# SCH_KTH7823_V1_0.net
KiCad netlist of a schematic drawn in EasyEDA
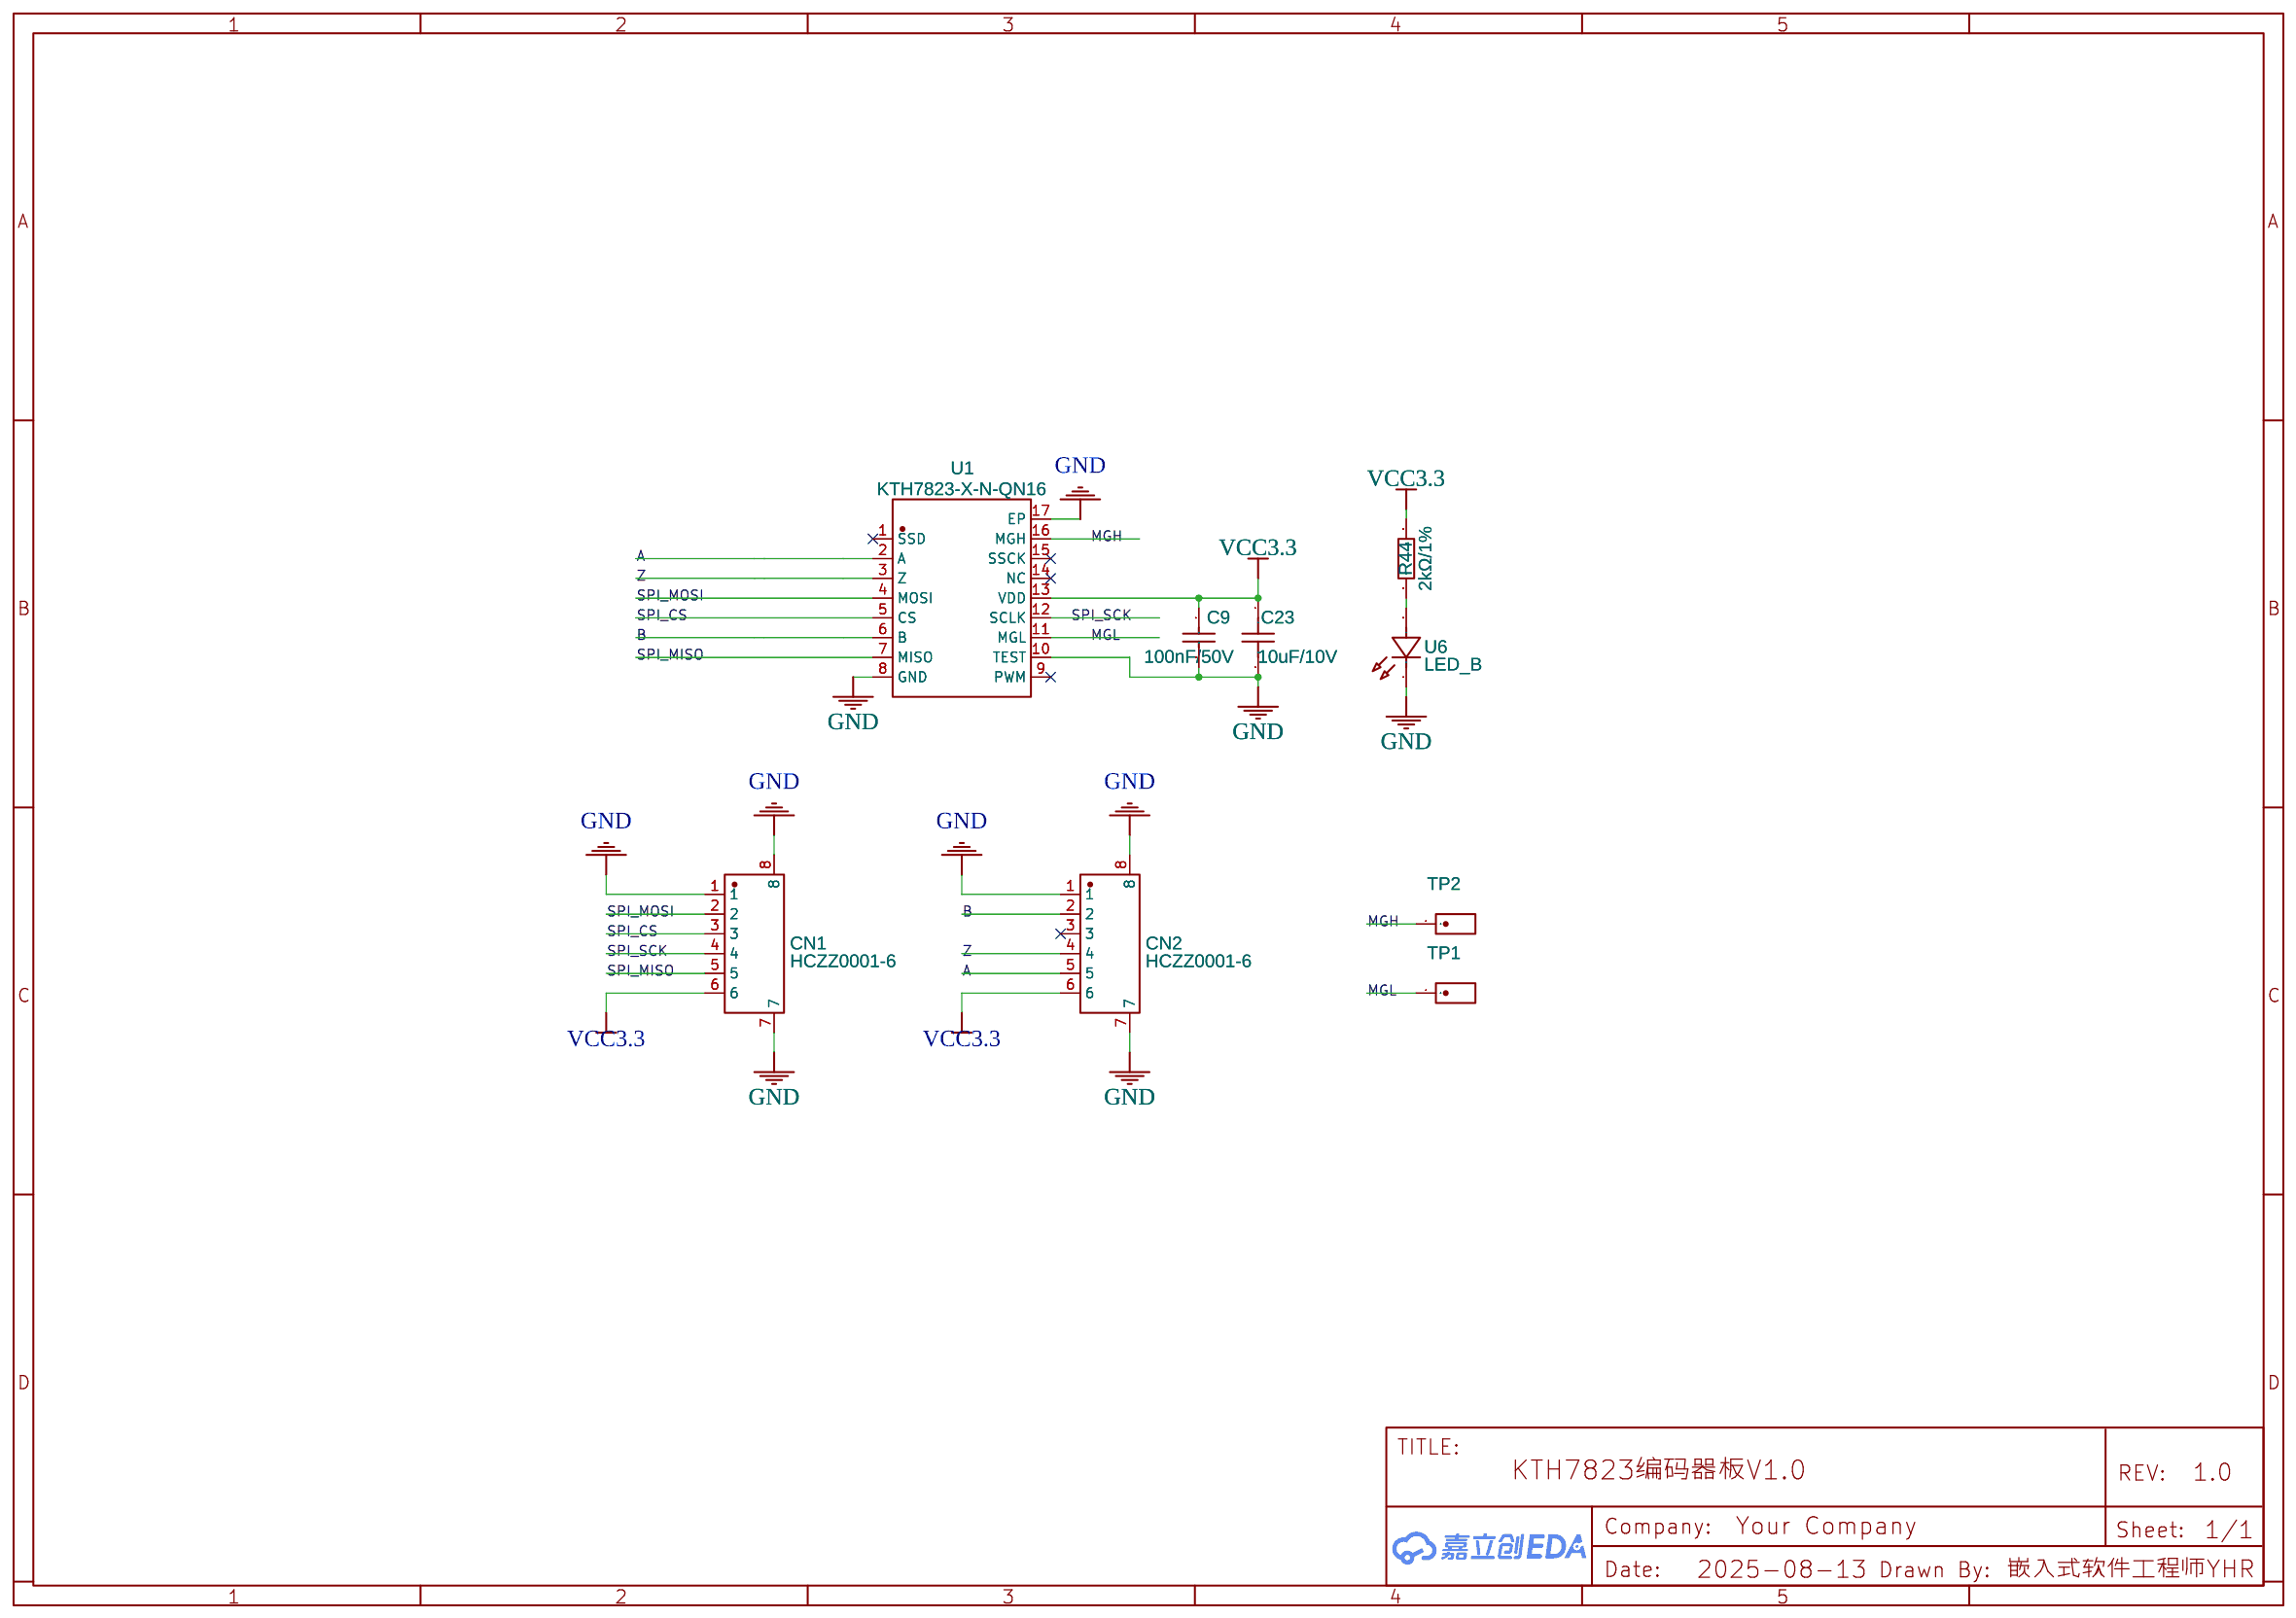
[diagram p0: schematic sheet]

(export (version "E")
  (design (tool "Eeschema 10.0.6"))
  (components
    (comp (ref "C9")
      (value "100nF/50V")
      (fields
        (field (name "Manufacturer Part") "CC0402KRX7R9BB104")
        (field (name "Manufacturer") "YAGEO(国巨)")
      )
      (libsource (lib "") (part "CC0402KRX7R9BB104"))
    )
    (comp (ref "C23")
      (value "10uF/10V")
      (fields
        (field (name "Manufacturer Part") "CL05A106MP5NUNC")
        (field (name "Manufacturer") "SAMSUNG(三星)")
      )
      (libsource (lib "") (part "CL05A106MP5NUNC_C315248"))
    )
    (comp (ref "CN1")
      (value "HCZZ0001-6")
      (fields (field (name "Manufacturer") "HC(虹成电子)"))
      (libsource (lib "") (part "HCZZ0001-6"))
    )
    (comp (ref "CN2")
      (value "HCZZ0001-6")
      (fields (field (name "Manufacturer") "HC(虹成电子)"))
      (libsource (lib "") (part "HCZZ0001-6"))
    )
    (comp (ref "R44")
      (value "2kΩ/1%")
      (fields (field (name "Manufacturer Part") "RC0402FR-072KL") (field (name "Manufacturer") "YAGEO(国巨)"))
      (libsource (lib "") (part "RC0402FR-072KL"))
    )
    (comp (ref "TP1") (value "5V") (libsource (lib "") (part "测试点")))
    (comp (ref "TP2") (value "5V") (libsource (lib "") (part "测试点")))
    (comp (ref "U1")
      (value "KTH7823-X-N-QN16")
      (fields (field (name "Manufacturer") "CONNTEK(昆泰芯)"))
      (libsource (lib "") (part "KTH7823-X-N-QN16"))
    )
    (comp (ref "U6")
      (value "LED_B")
      (fields (field (name "Manufacturer Part") "XL-1005UBC") (field (name "Manufacturer") "XINGLIGHT(成兴光)"))
      (libsource (lib "") (part "XL-1005UBC_C22355736"))
    )
  )
  (nets
    (net (code "1") (name "/A") (class "Default")
      (node (ref "CN2") (pin "5") (pinfunction "5_5") (pintype "unspecified"))
      (node (ref "U1") (pin "2") (pinfunction "A_2") (pintype "unspecified"))
    )
    (net (code "2") (name "/B") (class "Default")
      (node (ref "CN2") (pin "2") (pinfunction "2_2") (pintype "unspecified"))
      (node (ref "U1") (pin "6") (pinfunction "B_6") (pintype "unspecified"))
    )
    (net (code "3") (name "/MGH") (class "Default")
      (node (ref "TP2") (pin "1") (pinfunction "1_1") (pintype "unspecified"))
      (node (ref "U1") (pin "16") (pinfunction "MGH_16") (pintype "unspecified"))
    )
    (net (code "4") (name "/MGL") (class "Default")
      (node (ref "TP1") (pin "1") (pinfunction "1_1") (pintype "unspecified"))
      (node (ref "U1") (pin "11") (pinfunction "MGL_11") (pintype "unspecified"))
    )
    (net (code "5") (name "/SPI_CS") (class "Default")
      (node (ref "CN1") (pin "3") (pinfunction "3_3") (pintype "unspecified"))
      (node (ref "U1") (pin "5") (pinfunction "CS_5") (pintype "unspecified"))
    )
    (net (code "6") (name "/SPI_MISO") (class "Default")
      (node (ref "CN1") (pin "5") (pinfunction "5_5") (pintype "unspecified"))
      (node (ref "U1") (pin "7") (pinfunction "MISO_7") (pintype "unspecified"))
    )
    (net (code "7") (name "/SPI_MOSI") (class "Default")
      (node (ref "CN1") (pin "2") (pinfunction "2_2") (pintype "unspecified"))
      (node (ref "U1") (pin "4") (pinfunction "MOSI_4") (pintype "unspecified"))
    )
    (net (code "8") (name "/SPI_SCK") (class "Default")
      (node (ref "CN1") (pin "4") (pinfunction "4_4") (pintype "unspecified"))
      (node (ref "U1") (pin "12") (pinfunction "SCLK_12") (pintype "unspecified"))
    )
    (net (code "9") (name "/Z") (class "Default")
      (node (ref "CN2") (pin "4") (pinfunction "4_4") (pintype "unspecified"))
      (node (ref "U1") (pin "3") (pinfunction "Z_3") (pintype "unspecified"))
    )
    (net (code "10") (name "GND") (class "Default")
      (node (ref "C23") (pin "2") (pinfunction "2_2") (pintype "unspecified"))
      (node (ref "C9") (pin "2") (pinfunction "2_2") (pintype "input"))
      (node (ref "CN1") (pin "1") (pinfunction "1_1") (pintype "unspecified"))
      (node (ref "CN1") (pin "7") (pinfunction "7_7") (pintype "unspecified"))
      (node (ref "CN1") (pin "8") (pinfunction "8_8") (pintype "unspecified"))
      (node (ref "CN2") (pin "1") (pinfunction "1_1") (pintype "unspecified"))
      (node (ref "CN2") (pin "7") (pinfunction "7_7") (pintype "unspecified"))
      (node (ref "CN2") (pin "8") (pinfunction "8_8") (pintype "unspecified"))
      (node (ref "U1") (pin "10") (pinfunction "TEST_10") (pintype "unspecified"))
      (node (ref "U1") (pin "17") (pinfunction "EP_17") (pintype "unspecified"))
      (node (ref "U1") (pin "8") (pinfunction "GND_8") (pintype "unspecified"))
      (node (ref "U6") (pin "1") (pinfunction "K_1") (pintype "unspecified"))
    )
    (net (code "11") (name "Net-(U6-A)") (class "Default")
      (node (ref "R44") (pin "1") (pinfunction "1_1") (pintype "input"))
      (node (ref "U6") (pin "2") (pinfunction "A_2") (pintype "unspecified"))
    )
    (net (code "12") (name "VCC3.3") (class "Default")
      (node (ref "C23") (pin "1") (pinfunction "1_1") (pintype "unspecified"))
      (node (ref "C9") (pin "1") (pinfunction "1_1") (pintype "input"))
      (node (ref "CN1") (pin "6") (pinfunction "6_6") (pintype "unspecified"))
      (node (ref "CN2") (pin "6") (pinfunction "6_6") (pintype "unspecified"))
      (node (ref "R44") (pin "2") (pinfunction "2_2") (pintype "input"))
      (node (ref "U1") (pin "13") (pinfunction "VDD_13") (pintype "unspecified"))
    )
    (net (code "13") (name "unconnected-(CN2-Pad3)") (class "Default")
      (node (ref "CN2") (pin "3") (pinfunction "3_3") (pintype "unspecified+no_connect"))
    )
    (net (code "14") (name "unconnected-(U1-NC-Pad14)") (class "Default")
      (node (ref "U1") (pin "14") (pinfunction "NC_14") (pintype "unspecified+no_connect"))
    )
    (net (code "15") (name "unconnected-(U1-PWM-Pad9)") (class "Default")
      (node (ref "U1") (pin "9") (pinfunction "PWM_9") (pintype "unspecified+no_connect"))
    )
    (net (code "16") (name "unconnected-(U1-SSCK-Pad15)") (class "Default")
      (node (ref "U1") (pin "15") (pinfunction "SSCK_15") (pintype "unspecified+no_connect"))
    )
    (net (code "17") (name "unconnected-(U1-SSD-Pad1)") (class "Default")
      (node (ref "U1") (pin "1") (pinfunction "SSD_1") (pintype "unspecified+no_connect"))
    )
  )
)
